# 0x69-2.net
KiCad netlist of a schematic drawn in EAGLE
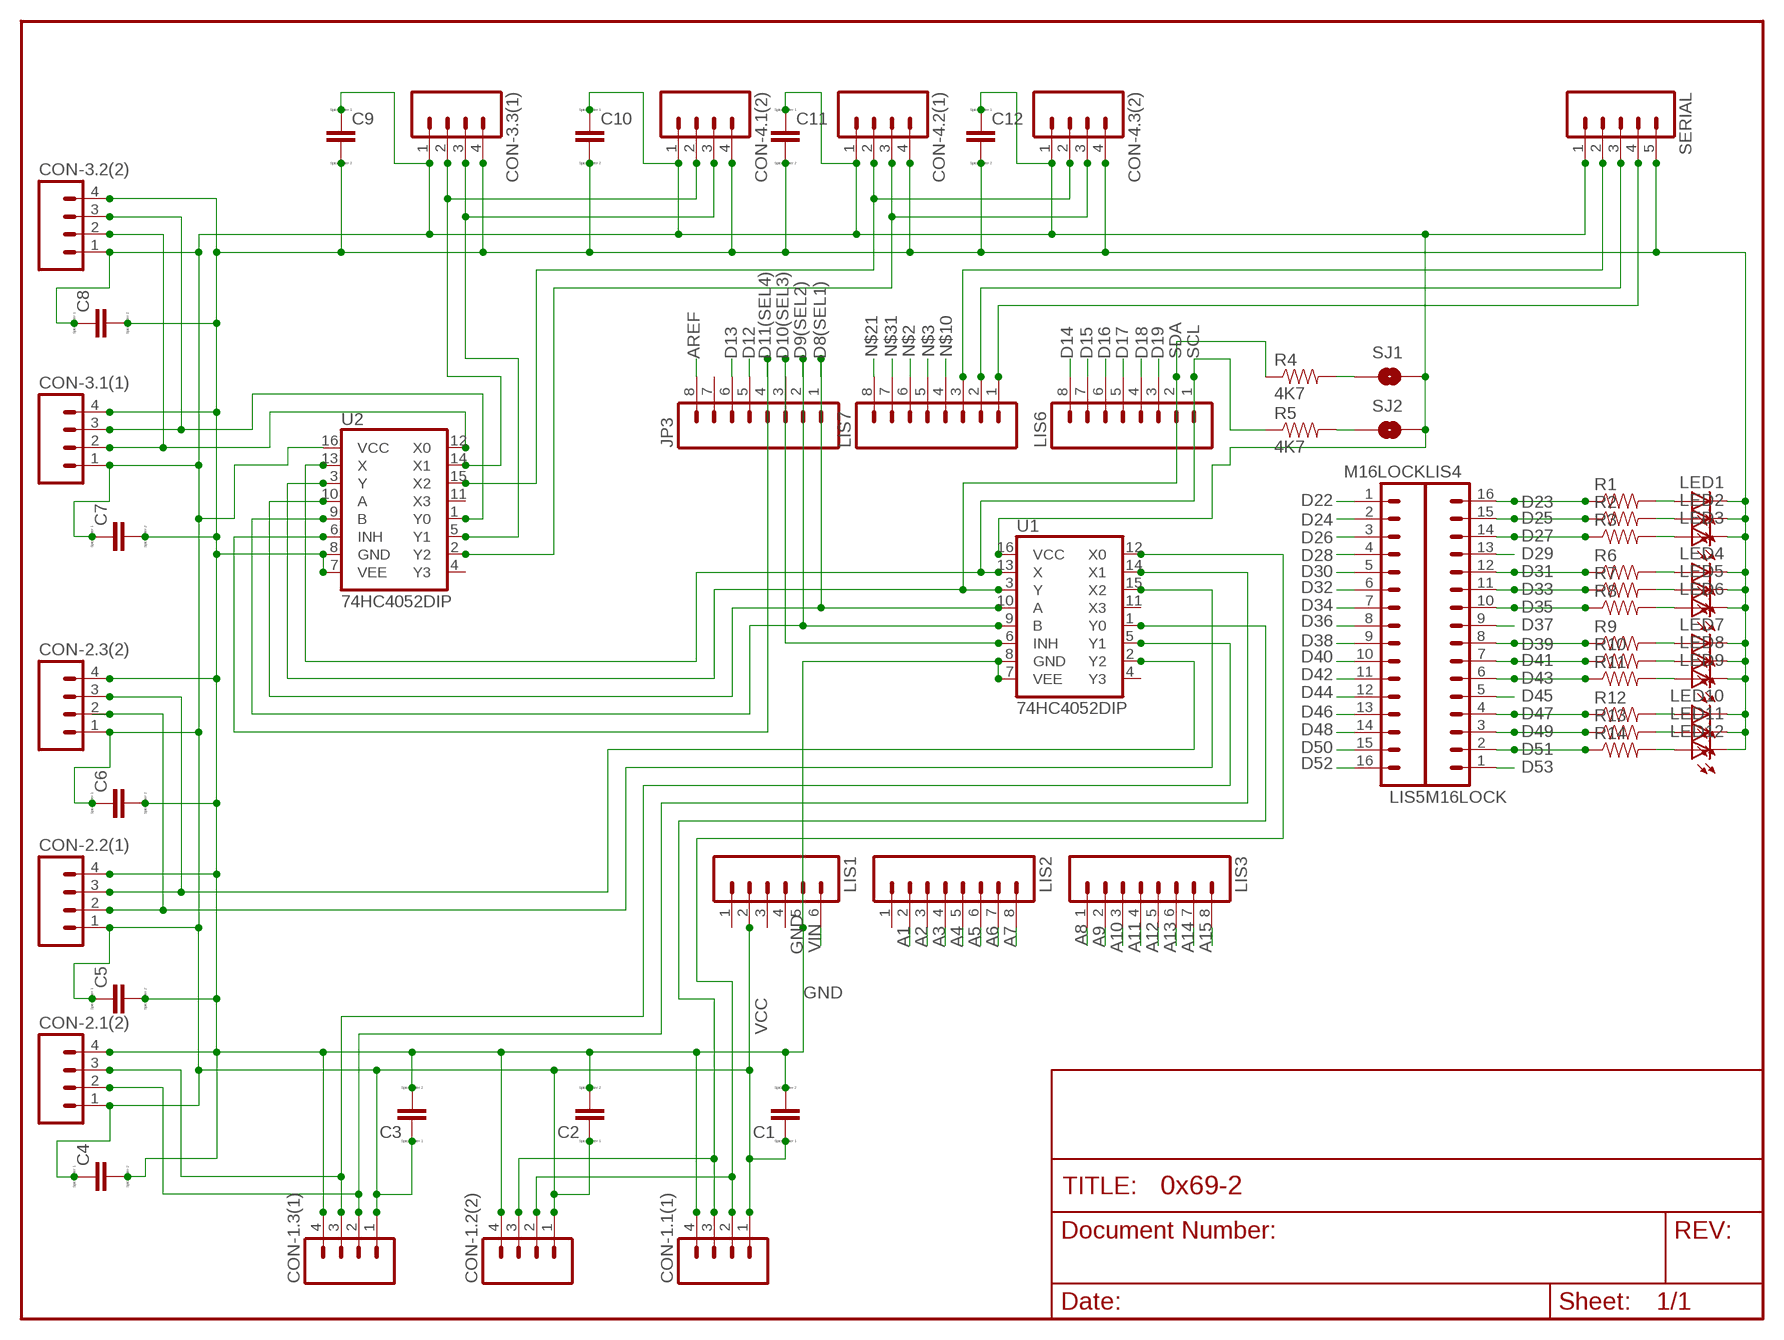
[diagram p0: schematic, sheet 1]

(export (version "E")
  (design (tool "Eeschema 10.0.6"))
  (components
    (comp (ref "C1") (value "C") (footprint "eagle-import:C0805") (libsource (lib "eagle-import") (part "C")))
    (comp (ref "C2") (value "C") (footprint "eagle-import:C0805") (libsource (lib "eagle-import") (part "C")))
    (comp (ref "C3") (value "C") (footprint "eagle-import:C0805") (libsource (lib "eagle-import") (part "C")))
    (comp (ref "C4") (value "C") (footprint "eagle-import:C0805") (libsource (lib "eagle-import") (part "C")))
    (comp (ref "C5") (value "C") (footprint "eagle-import:C0805") (libsource (lib "eagle-import") (part "C")))
    (comp (ref "C6") (value "C") (footprint "eagle-import:C0805") (libsource (lib "eagle-import") (part "C")))
    (comp (ref "C7") (value "C") (footprint "eagle-import:C0805") (libsource (lib "eagle-import") (part "C")))
    (comp (ref "C8") (value "C") (footprint "eagle-import:C0805") (libsource (lib "eagle-import") (part "C")))
    (comp (ref "C9") (value "C") (footprint "eagle-import:C0805") (libsource (lib "eagle-import") (part "C")))
    (comp (ref "C10")
      (value "C")
      (footprint "eagle-import:C0805")
      (libsource (lib "eagle-import") (part "C"))
    )
    (comp (ref "C11")
      (value "C")
      (footprint "eagle-import:C0805")
      (libsource (lib "eagle-import") (part "C"))
    )
    (comp (ref "C12")
      (value "C")
      (footprint "eagle-import:C0805")
      (libsource (lib "eagle-import") (part "C"))
    )
    (comp (ref "CON-1.1(1)")
      (value "M04LONGPADS")
      (footprint "eagle-import:1X04_LONGPADS")
      (libsource (lib "eagle-import") (part "M04LONGPADS"))
    )
    (comp (ref "CON-1.2(2)")
      (value "M04LONGPADS")
      (footprint "eagle-import:1X04_LONGPADS")
      (libsource (lib "eagle-import") (part "M04LONGPADS"))
    )
    (comp (ref "CON-1.3(1)")
      (value "M04LONGPADS")
      (footprint "eagle-import:1X04_LONGPADS")
      (libsource (lib "eagle-import") (part "M04LONGPADS"))
    )
    (comp (ref "CON-2.1(2)")
      (value "M04LONGPADS")
      (footprint "eagle-import:1X04_LONGPADS")
      (libsource (lib "eagle-import") (part "M04LONGPADS"))
    )
    (comp (ref "CON-2.2(1)")
      (value "M04LONGPADS")
      (footprint "eagle-import:1X04_LONGPADS")
      (libsource (lib "eagle-import") (part "M04LONGPADS"))
    )
    (comp (ref "CON-2.3(2)")
      (value "M04LONGPADS")
      (footprint "eagle-import:1X04_LONGPADS")
      (libsource (lib "eagle-import") (part "M04LONGPADS"))
    )
    (comp (ref "CON-3.1(1)")
      (value "M04LONGPADS")
      (footprint "eagle-import:1X04_LONGPADS")
      (libsource (lib "eagle-import") (part "M04LONGPADS"))
    )
    (comp (ref "CON-3.2(2)")
      (value "M04LONGPADS")
      (footprint "eagle-import:1X04_LONGPADS")
      (libsource (lib "eagle-import") (part "M04LONGPADS"))
    )
    (comp (ref "CON-3.3(1)")
      (value "M04LONGPADS")
      (footprint "eagle-import:1X04_LONGPADS")
      (libsource (lib "eagle-import") (part "M04LONGPADS"))
    )
    (comp (ref "CON-4.1(2)")
      (value "M04LONGPADS")
      (footprint "eagle-import:1X04_LONGPADS")
      (libsource (lib "eagle-import") (part "M04LONGPADS"))
    )
    (comp (ref "CON-4.2(1)")
      (value "M04LONGPADS")
      (footprint "eagle-import:1X04_LONGPADS")
      (libsource (lib "eagle-import") (part "M04LONGPADS"))
    )
    (comp (ref "CON-4.3(2)")
      (value "M04LONGPADS")
      (footprint "eagle-import:1X04_LONGPADS")
      (libsource (lib "eagle-import") (part "M04LONGPADS"))
    )
    (comp (ref "JP3")
      (value "M08LOCK")
      (footprint "eagle-import:1X08_LOCK")
      (libsource (lib "eagle-import") (part "M08LOCK"))
    )
    (comp (ref "LED1")
      (value "LED-FKIT-1206")
      (footprint "eagle-import:FKIT-LED-1206")
      (libsource (lib "eagle-import") (part "LED-FKIT-1206"))
    )
    (comp (ref "LED2")
      (value "LED-FKIT-1206")
      (footprint "eagle-import:FKIT-LED-1206")
      (libsource (lib "eagle-import") (part "LED-FKIT-1206"))
    )
    (comp (ref "LED3")
      (value "LED-FKIT-1206")
      (footprint "eagle-import:FKIT-LED-1206")
      (libsource (lib "eagle-import") (part "LED-FKIT-1206"))
    )
    (comp (ref "LED4")
      (value "LED-FKIT-1206")
      (footprint "eagle-import:FKIT-LED-1206")
      (libsource (lib "eagle-import") (part "LED-FKIT-1206"))
    )
    (comp (ref "LED5")
      (value "LED-FKIT-1206")
      (footprint "eagle-import:FKIT-LED-1206")
      (libsource (lib "eagle-import") (part "LED-FKIT-1206"))
    )
    (comp (ref "LED6")
      (value "LED-FKIT-1206")
      (footprint "eagle-import:FKIT-LED-1206")
      (libsource (lib "eagle-import") (part "LED-FKIT-1206"))
    )
    (comp (ref "LED7")
      (value "LED-FKIT-1206")
      (footprint "eagle-import:FKIT-LED-1206")
      (libsource (lib "eagle-import") (part "LED-FKIT-1206"))
    )
    (comp (ref "LED8")
      (value "LED-FKIT-1206")
      (footprint "eagle-import:FKIT-LED-1206")
      (libsource (lib "eagle-import") (part "LED-FKIT-1206"))
    )
    (comp (ref "LED9")
      (value "LED-FKIT-1206")
      (footprint "eagle-import:FKIT-LED-1206")
      (libsource (lib "eagle-import") (part "LED-FKIT-1206"))
    )
    (comp (ref "LED10")
      (value "LED-FKIT-1206")
      (footprint "eagle-import:FKIT-LED-1206")
      (libsource (lib "eagle-import") (part "LED-FKIT-1206"))
    )
    (comp (ref "LED11")
      (value "LED-FKIT-1206")
      (footprint "eagle-import:FKIT-LED-1206")
      (libsource (lib "eagle-import") (part "LED-FKIT-1206"))
    )
    (comp (ref "LED12")
      (value "LED-FKIT-1206")
      (footprint "eagle-import:FKIT-LED-1206")
      (libsource (lib "eagle-import") (part "LED-FKIT-1206"))
    )
    (comp (ref "LIS1")
      (value "M06LOCK")
      (footprint "eagle-import:1X06_LOCK")
      (libsource (lib "eagle-import") (part "M06LOCK"))
    )
    (comp (ref "LIS2")
      (value "M08LOCK")
      (footprint "eagle-import:1X08_LOCK")
      (libsource (lib "eagle-import") (part "M08LOCK"))
    )
    (comp (ref "LIS3")
      (value "M08LOCK")
      (footprint "eagle-import:1X08_LOCK")
      (libsource (lib "eagle-import") (part "M08LOCK"))
    )
    (comp (ref "LIS4")
      (value "M16LOCK")
      (footprint "eagle-import:1X16_LOCK")
      (libsource (lib "eagle-import") (part "M16LOCK"))
    )
    (comp (ref "LIS5")
      (value "M16LOCK")
      (footprint "eagle-import:1X16_LOCK")
      (libsource (lib "eagle-import") (part "M16LOCK"))
    )
    (comp (ref "LIS6")
      (value "M08LOCK")
      (footprint "eagle-import:1X08_LOCK")
      (libsource (lib "eagle-import") (part "M08LOCK"))
    )
    (comp (ref "LIS7")
      (value "M08LOCK")
      (footprint "eagle-import:1X08_LOCK")
      (libsource (lib "eagle-import") (part "M08LOCK"))
    )
    (comp (ref "R1")
      (value "0.22OHM1/4W1%(0805)")
      (footprint "eagle-import:0805")
      (libsource (lib "eagle-import") (part "0.22OHM1/4W1%(0805)"))
    )
    (comp (ref "R2")
      (value "0.22OHM1/4W1%(0805)")
      (footprint "eagle-import:0805")
      (libsource (lib "eagle-import") (part "0.22OHM1/4W1%(0805)"))
    )
    (comp (ref "R3")
      (value "0.22OHM1/4W1%(0805)")
      (footprint "eagle-import:0805")
      (libsource (lib "eagle-import") (part "0.22OHM1/4W1%(0805)"))
    )
    (comp (ref "R4")
      (value "4K7")
      (footprint "eagle-import:0603-RES")
      (libsource (lib "eagle-import") (part "47KOHM1/10W1%(0603)"))
    )
    (comp (ref "R5")
      (value "4K7")
      (footprint "eagle-import:0603-RES")
      (libsource (lib "eagle-import") (part "47KOHM1/10W1%(0603)"))
    )
    (comp (ref "R6")
      (value "0.22OHM1/4W1%(0805)")
      (footprint "eagle-import:0805")
      (libsource (lib "eagle-import") (part "0.22OHM1/4W1%(0805)"))
    )
    (comp (ref "R7")
      (value "0.22OHM1/4W1%(0805)")
      (footprint "eagle-import:0805")
      (libsource (lib "eagle-import") (part "0.22OHM1/4W1%(0805)"))
    )
    (comp (ref "R8")
      (value "0.22OHM1/4W1%(0805)")
      (footprint "eagle-import:0805")
      (libsource (lib "eagle-import") (part "0.22OHM1/4W1%(0805)"))
    )
    (comp (ref "R9")
      (value "0.22OHM1/4W1%(0805)")
      (footprint "eagle-import:0805")
      (libsource (lib "eagle-import") (part "0.22OHM1/4W1%(0805)"))
    )
    (comp (ref "R10")
      (value "0.22OHM1/4W1%(0805)")
      (footprint "eagle-import:0805")
      (libsource (lib "eagle-import") (part "0.22OHM1/4W1%(0805)"))
    )
    (comp (ref "R11")
      (value "0.22OHM1/4W1%(0805)")
      (footprint "eagle-import:0805")
      (libsource (lib "eagle-import") (part "0.22OHM1/4W1%(0805)"))
    )
    (comp (ref "R12")
      (value "0.22OHM1/4W1%(0805)")
      (footprint "eagle-import:0805")
      (libsource (lib "eagle-import") (part "0.22OHM1/4W1%(0805)"))
    )
    (comp (ref "R13")
      (value "0.22OHM1/4W1%(0805)")
      (footprint "eagle-import:0805")
      (libsource (lib "eagle-import") (part "0.22OHM1/4W1%(0805)"))
    )
    (comp (ref "R14")
      (value "0.22OHM1/4W1%(0805)")
      (footprint "eagle-import:0805")
      (libsource (lib "eagle-import") (part "0.22OHM1/4W1%(0805)"))
    )
    (comp (ref "SERIAL")
      (value "M05PTH_LONGPADS")
      (footprint "eagle-import:1X05_LONGPADS")
      (libsource (lib "eagle-import") (part "M05PTH_LONGPADS"))
    )
    (comp (ref "SJ1")
      (value "SOLDERJUMPERNC")
      (footprint "eagle-import:SJ-NC")
      (libsource (lib "eagle-import") (part "SOLDERJUMPERNC"))
    )
    (comp (ref "SJ2")
      (value "SOLDERJUMPERNC")
      (footprint "eagle-import:SJ-NC")
      (libsource (lib "eagle-import") (part "SOLDERJUMPERNC"))
    )
    (comp (ref "U1")
      (value "74HC4052DIP")
      (footprint "eagle-import:DIL16")
      (libsource (lib "eagle-import") (part "74HC4052DIP"))
    )
    (comp (ref "U2")
      (value "74HC4052DIP")
      (footprint "eagle-import:DIL16")
      (libsource (lib "eagle-import") (part "74HC4052DIP"))
    )
  )
  (nets
    (net (code "1") (name "/A1") (class "Default")
      (node (ref "LIS2") (pin "2") (pinfunction "2_2") (pintype "passive"))
    )
    (net (code "2") (name "/A2") (class "Default")
      (node (ref "LIS2") (pin "3") (pinfunction "3_3") (pintype "passive"))
    )
    (net (code "3") (name "/A3") (class "Default")
      (node (ref "LIS2") (pin "4") (pinfunction "4_4") (pintype "passive"))
    )
    (net (code "4") (name "/A4") (class "Default")
      (node (ref "LIS2") (pin "5") (pinfunction "5_5") (pintype "passive"))
    )
    (net (code "5") (name "/A5") (class "Default")
      (node (ref "LIS2") (pin "6") (pinfunction "6_6") (pintype "passive"))
    )
    (net (code "6") (name "/A6") (class "Default")
      (node (ref "LIS2") (pin "7") (pinfunction "7_7") (pintype "passive"))
    )
    (net (code "7") (name "/A7") (class "Default")
      (node (ref "LIS2") (pin "8") (pinfunction "8_8") (pintype "passive"))
    )
    (net (code "8") (name "/A8") (class "Default")
      (node (ref "LIS3") (pin "1") (pinfunction "1_1") (pintype "passive"))
    )
    (net (code "9") (name "/A9") (class "Default")
      (node (ref "LIS3") (pin "2") (pinfunction "2_2") (pintype "passive"))
    )
    (net (code "10") (name "/A10") (class "Default")
      (node (ref "LIS3") (pin "3") (pinfunction "3_3") (pintype "passive"))
    )
    (net (code "11") (name "/A11") (class "Default")
      (node (ref "LIS3") (pin "4") (pinfunction "4_4") (pintype "passive"))
    )
    (net (code "12") (name "/A12") (class "Default")
      (node (ref "LIS3") (pin "5") (pinfunction "5_5") (pintype "passive"))
    )
    (net (code "13") (name "/A13") (class "Default")
      (node (ref "LIS3") (pin "6") (pinfunction "6_6") (pintype "passive"))
    )
    (net (code "14") (name "/A14") (class "Default")
      (node (ref "LIS3") (pin "7") (pinfunction "7_7") (pintype "passive"))
    )
    (net (code "15") (name "/A15") (class "Default")
      (node (ref "LIS3") (pin "8") (pinfunction "8_8") (pintype "passive"))
    )
    (net (code "16") (name "/AREF") (class "Default")
      (node (ref "JP3") (pin "8") (pinfunction "8_8") (pintype "passive"))
    )
    (net (code "17") (name "/D8(SEL1)") (class "Default")
      (node (ref "JP3") (pin "1") (pinfunction "1_1") (pintype "passive"))
      (node (ref "U1") (pin "10") (pinfunction "A_10") (pintype "input"))
      (node (ref "U2") (pin "10") (pinfunction "A_10") (pintype "input"))
    )
    (net (code "18") (name "/D9(SEL2)") (class "Default")
      (node (ref "JP3") (pin "2") (pinfunction "2_2") (pintype "passive"))
      (node (ref "U1") (pin "9") (pinfunction "B_9") (pintype "input"))
      (node (ref "U2") (pin "9") (pinfunction "B_9") (pintype "input"))
    )
    (net (code "19") (name "/D10(SEL3)") (class "Default")
      (node (ref "JP3") (pin "3") (pinfunction "3_3") (pintype "passive"))
      (node (ref "U1") (pin "6") (pinfunction "INH_6") (pintype "input"))
    )
    (net (code "20") (name "/D11(SEL4)") (class "Default")
      (node (ref "JP3") (pin "4") (pinfunction "4_4") (pintype "passive"))
      (node (ref "U2") (pin "6") (pinfunction "INH_6") (pintype "input"))
    )
    (net (code "21") (name "/D12") (class "Default")
      (node (ref "JP3") (pin "5") (pinfunction "5_5") (pintype "passive"))
    )
    (net (code "22") (name "/D13") (class "Default")
      (node (ref "JP3") (pin "6") (pinfunction "6_6") (pintype "passive"))
    )
    (net (code "23") (name "/D14") (class "Default")
      (node (ref "LIS6") (pin "8") (pinfunction "8_8") (pintype "passive"))
    )
    (net (code "24") (name "/D15") (class "Default")
      (node (ref "LIS6") (pin "7") (pinfunction "7_7") (pintype "passive"))
    )
    (net (code "25") (name "/D16") (class "Default")
      (node (ref "LIS6") (pin "6") (pinfunction "6_6") (pintype "passive"))
    )
    (net (code "26") (name "/D17") (class "Default")
      (node (ref "LIS6") (pin "5") (pinfunction "5_5") (pintype "passive"))
    )
    (net (code "27") (name "/D18") (class "Default")
      (node (ref "LIS6") (pin "4") (pinfunction "4_4") (pintype "passive"))
    )
    (net (code "28") (name "/D19") (class "Default")
      (node (ref "LIS6") (pin "3") (pinfunction "3_3") (pintype "passive"))
    )
    (net (code "29") (name "/D22") (class "Default")
      (node (ref "LIS5") (pin "1") (pinfunction "1_1") (pintype "passive"))
    )
    (net (code "30") (name "/D23") (class "Default")
      (node (ref "LIS4") (pin "16") (pinfunction "16_16") (pintype "passive"))
      (node (ref "R1") (pin "1") (pinfunction "1_1") (pintype "passive"))
    )
    (net (code "31") (name "/D24") (class "Default")
      (node (ref "LIS5") (pin "2") (pinfunction "2_2") (pintype "passive"))
    )
    (net (code "32") (name "/D25") (class "Default")
      (node (ref "LIS4") (pin "15") (pinfunction "15_15") (pintype "passive"))
      (node (ref "R2") (pin "1") (pinfunction "1_1") (pintype "passive"))
    )
    (net (code "33") (name "/D26") (class "Default")
      (node (ref "LIS5") (pin "3") (pinfunction "3_3") (pintype "passive"))
    )
    (net (code "34") (name "/D27") (class "Default")
      (node (ref "LIS4") (pin "14") (pinfunction "14_14") (pintype "passive"))
      (node (ref "R3") (pin "1") (pinfunction "1_1") (pintype "passive"))
    )
    (net (code "35") (name "/D28") (class "Default")
      (node (ref "LIS5") (pin "4") (pinfunction "4_4") (pintype "passive"))
    )
    (net (code "36") (name "/D29") (class "Default")
      (node (ref "LIS4") (pin "13") (pinfunction "13_13") (pintype "passive"))
    )
    (net (code "37") (name "/D30") (class "Default")
      (node (ref "LIS5") (pin "5") (pinfunction "5_5") (pintype "passive"))
    )
    (net (code "38") (name "/D31") (class "Default")
      (node (ref "LIS4") (pin "12") (pinfunction "12_12") (pintype "passive"))
      (node (ref "R6") (pin "1") (pinfunction "1_1") (pintype "passive"))
    )
    (net (code "39") (name "/D32") (class "Default")
      (node (ref "LIS5") (pin "6") (pinfunction "6_6") (pintype "passive"))
    )
    (net (code "40") (name "/D33") (class "Default")
      (node (ref "LIS4") (pin "11") (pinfunction "11_11") (pintype "passive"))
      (node (ref "R7") (pin "1") (pinfunction "1_1") (pintype "passive"))
    )
    (net (code "41") (name "/D34") (class "Default")
      (node (ref "LIS5") (pin "7") (pinfunction "7_7") (pintype "passive"))
    )
    (net (code "42") (name "/D35") (class "Default")
      (node (ref "LIS4") (pin "10") (pinfunction "10_10") (pintype "passive"))
      (node (ref "R8") (pin "1") (pinfunction "1_1") (pintype "passive"))
    )
    (net (code "43") (name "/D36") (class "Default")
      (node (ref "LIS5") (pin "8") (pinfunction "8_8") (pintype "passive"))
    )
    (net (code "44") (name "/D37") (class "Default")
      (node (ref "LIS4") (pin "9") (pinfunction "9_9") (pintype "passive"))
    )
    (net (code "45") (name "/D38") (class "Default")
      (node (ref "LIS5") (pin "9") (pinfunction "9_9") (pintype "passive"))
    )
    (net (code "46") (name "/D39") (class "Default")
      (node (ref "LIS4") (pin "8") (pinfunction "8_8") (pintype "passive"))
      (node (ref "R9") (pin "1") (pinfunction "1_1") (pintype "passive"))
    )
    (net (code "47") (name "/D40") (class "Default")
      (node (ref "LIS5") (pin "10") (pinfunction "10_10") (pintype "passive"))
    )
    (net (code "48") (name "/D41") (class "Default")
      (node (ref "LIS4") (pin "7") (pinfunction "7_7") (pintype "passive"))
      (node (ref "R10") (pin "1") (pinfunction "1_1") (pintype "passive"))
    )
    (net (code "49") (name "/D42") (class "Default")
      (node (ref "LIS5") (pin "11") (pinfunction "11_11") (pintype "passive"))
    )
    (net (code "50") (name "/D43") (class "Default")
      (node (ref "LIS4") (pin "6") (pinfunction "6_6") (pintype "passive"))
      (node (ref "R11") (pin "1") (pinfunction "1_1") (pintype "passive"))
    )
    (net (code "51") (name "/D44") (class "Default")
      (node (ref "LIS5") (pin "12") (pinfunction "12_12") (pintype "passive"))
    )
    (net (code "52") (name "/D45") (class "Default")
      (node (ref "LIS4") (pin "5") (pinfunction "5_5") (pintype "passive"))
    )
    (net (code "53") (name "/D46") (class "Default")
      (node (ref "LIS5") (pin "13") (pinfunction "13_13") (pintype "passive"))
    )
    (net (code "54") (name "/D47") (class "Default")
      (node (ref "LIS4") (pin "4") (pinfunction "4_4") (pintype "passive"))
      (node (ref "R12") (pin "1") (pinfunction "1_1") (pintype "passive"))
    )
    (net (code "55") (name "/D48") (class "Default")
      (node (ref "LIS5") (pin "14") (pinfunction "14_14") (pintype "passive"))
    )
    (net (code "56") (name "/D49") (class "Default")
      (node (ref "LIS4") (pin "3") (pinfunction "3_3") (pintype "passive"))
      (node (ref "R13") (pin "1") (pinfunction "1_1") (pintype "passive"))
    )
    (net (code "57") (name "/D50") (class "Default")
      (node (ref "LIS5") (pin "15") (pinfunction "15_15") (pintype "passive"))
    )
    (net (code "58") (name "/D51") (class "Default")
      (node (ref "LIS4") (pin "2") (pinfunction "2_2") (pintype "passive"))
      (node (ref "R14") (pin "1") (pinfunction "1_1") (pintype "passive"))
    )
    (net (code "59") (name "/D52") (class "Default")
      (node (ref "LIS5") (pin "16") (pinfunction "16_16") (pintype "passive"))
    )
    (net (code "60") (name "/D53") (class "Default")
      (node (ref "LIS4") (pin "1") (pinfunction "1_1") (pintype "passive"))
    )
    (net (code "61") (name "/GND") (class "Default")
      (node (ref "C1") (pin "2") (pinfunction "2_2") (pintype "passive"))
      (node (ref "C10") (pin "2") (pinfunction "2_2") (pintype "passive"))
      (node (ref "C11") (pin "2") (pinfunction "2_2") (pintype "passive"))
      (node (ref "C12") (pin "2") (pinfunction "2_2") (pintype "passive"))
      (node (ref "C2") (pin "2") (pinfunction "2_2") (pintype "passive"))
      (node (ref "C3") (pin "2") (pinfunction "2_2") (pintype "passive"))
      (node (ref "C4") (pin "2") (pinfunction "2_2") (pintype "passive"))
      (node (ref "C5") (pin "2") (pinfunction "2_2") (pintype "passive"))
      (node (ref "C6") (pin "2") (pinfunction "2_2") (pintype "passive"))
      (node (ref "C7") (pin "2") (pinfunction "2_2") (pintype "passive"))
      (node (ref "C8") (pin "2") (pinfunction "2_2") (pintype "passive"))
      (node (ref "C9") (pin "2") (pinfunction "2_2") (pintype "passive"))
      (node (ref "CON-1.1(1)") (pin "4") (pinfunction "4_4") (pintype "passive"))
      (node (ref "CON-1.2(2)") (pin "4") (pinfunction "4_4") (pintype "passive"))
      (node (ref "CON-1.3(1)") (pin "4") (pinfunction "4_4") (pintype "passive"))
      (node (ref "CON-2.1(2)") (pin "4") (pinfunction "4_4") (pintype "passive"))
      (node (ref "CON-2.2(1)") (pin "4") (pinfunction "4_4") (pintype "passive"))
      (node (ref "CON-2.3(2)") (pin "4") (pinfunction "4_4") (pintype "passive"))
      (node (ref "CON-3.1(1)") (pin "4") (pinfunction "4_4") (pintype "passive"))
      (node (ref "CON-3.2(2)") (pin "4") (pinfunction "4_4") (pintype "passive"))
      (node (ref "CON-3.3(1)") (pin "4") (pinfunction "4_4") (pintype "passive"))
      (node (ref "CON-4.1(2)") (pin "4") (pinfunction "4_4") (pintype "passive"))
      (node (ref "CON-4.2(1)") (pin "4") (pinfunction "4_4") (pintype "passive"))
      (node (ref "CON-4.3(2)") (pin "4") (pinfunction "4_4") (pintype "passive"))
      (node (ref "LED1") (pin "C") (pinfunction "C_C") (pintype "passive"))
      (node (ref "LED10") (pin "C") (pinfunction "C_C") (pintype "passive"))
      (node (ref "LED11") (pin "C") (pinfunction "C_C") (pintype "passive"))
      (node (ref "LED12") (pin "C") (pinfunction "C_C") (pintype "passive"))
      (node (ref "LED2") (pin "C") (pinfunction "C_C") (pintype "passive"))
      (node (ref "LED3") (pin "C") (pinfunction "C_C") (pintype "passive"))
      (node (ref "LED4") (pin "C") (pinfunction "C_C") (pintype "passive"))
      (node (ref "LED5") (pin "C") (pinfunction "C_C") (pintype "passive"))
      (node (ref "LED6") (pin "C") (pinfunction "C_C") (pintype "passive"))
      (node (ref "LED7") (pin "C") (pinfunction "C_C") (pintype "passive"))
      (node (ref "LED8") (pin "C") (pinfunction "C_C") (pintype "passive"))
      (node (ref "LED9") (pin "C") (pinfunction "C_C") (pintype "passive"))
      (node (ref "LIS1") (pin "5") (pinfunction "5_5") (pintype "passive"))
      (node (ref "SERIAL") (pin "5") (pinfunction "5_5") (pintype "passive"))
      (node (ref "U1") (pin "7") (pinfunction "VEE_7") (pintype "power_in"))
      (node (ref "U1") (pin "8") (pinfunction "GND_8") (pintype "power_in"))
      (node (ref "U2") (pin "7") (pinfunction "VEE_7") (pintype "power_in"))
      (node (ref "U2") (pin "8") (pinfunction "GND_8") (pintype "power_in"))
    )
    (net (code "62") (name "/N$2") (class "Default")
      (node (ref "LIS7") (pin "6") (pinfunction "6_6") (pintype "passive"))
    )
    (net (code "63") (name "/N$3") (class "Default")
      (node (ref "LIS7") (pin "5") (pinfunction "5_5") (pintype "passive"))
    )
    (net (code "64") (name "/N$10") (class "Default")
      (node (ref "LIS7") (pin "4") (pinfunction "4_4") (pintype "passive"))
    )
    (net (code "65") (name "/N$21") (class "Default")
      (node (ref "LIS7") (pin "8") (pinfunction "8_8") (pintype "passive"))
    )
    (net (code "66") (name "/N$31") (class "Default")
      (node (ref "LIS7") (pin "7") (pinfunction "7_7") (pintype "passive"))
    )
    (net (code "67") (name "/SCL") (class "Default")
      (node (ref "LIS6") (pin "1") (pinfunction "1_1") (pintype "passive"))
      (node (ref "R5") (pin "1") (pinfunction "1_1") (pintype "passive"))
      (node (ref "U1") (pin "13") (pinfunction "X_13") (pintype "bidirectional"))
      (node (ref "U2") (pin "13") (pinfunction "X_13") (pintype "bidirectional"))
    )
    (net (code "68") (name "/SDA") (class "Default")
      (node (ref "LIS6") (pin "2") (pinfunction "2_2") (pintype "passive"))
      (node (ref "R4") (pin "1") (pinfunction "1_1") (pintype "passive"))
      (node (ref "U1") (pin "3") (pinfunction "Y_3") (pintype "bidirectional"))
      (node (ref "U2") (pin "3") (pinfunction "Y_3") (pintype "bidirectional"))
    )
    (net (code "69") (name "/VCC") (class "Default")
      (node (ref "C1") (pin "1") (pinfunction "1_1") (pintype "passive"))
      (node (ref "C10") (pin "1") (pinfunction "1_1") (pintype "passive"))
      (node (ref "C11") (pin "1") (pinfunction "1_1") (pintype "passive"))
      (node (ref "C12") (pin "1") (pinfunction "1_1") (pintype "passive"))
      (node (ref "C2") (pin "1") (pinfunction "1_1") (pintype "passive"))
      (node (ref "C3") (pin "1") (pinfunction "1_1") (pintype "passive"))
      (node (ref "C4") (pin "1") (pinfunction "1_1") (pintype "passive"))
      (node (ref "C5") (pin "1") (pinfunction "1_1") (pintype "passive"))
      (node (ref "C6") (pin "1") (pinfunction "1_1") (pintype "passive"))
      (node (ref "C7") (pin "1") (pinfunction "1_1") (pintype "passive"))
      (node (ref "C8") (pin "1") (pinfunction "1_1") (pintype "passive"))
      (node (ref "C9") (pin "1") (pinfunction "1_1") (pintype "passive"))
      (node (ref "CON-1.1(1)") (pin "1") (pinfunction "1_1") (pintype "passive"))
      (node (ref "CON-1.2(2)") (pin "1") (pinfunction "1_1") (pintype "passive"))
      (node (ref "CON-1.3(1)") (pin "1") (pinfunction "1_1") (pintype "passive"))
      (node (ref "CON-2.1(2)") (pin "1") (pinfunction "1_1") (pintype "passive"))
      (node (ref "CON-2.2(1)") (pin "1") (pinfunction "1_1") (pintype "passive"))
      (node (ref "CON-2.3(2)") (pin "1") (pinfunction "1_1") (pintype "passive"))
      (node (ref "CON-3.1(1)") (pin "1") (pinfunction "1_1") (pintype "passive"))
      (node (ref "CON-3.2(2)") (pin "1") (pinfunction "1_1") (pintype "passive"))
      (node (ref "CON-3.3(1)") (pin "1") (pinfunction "1_1") (pintype "passive"))
      (node (ref "CON-4.1(2)") (pin "1") (pinfunction "1_1") (pintype "passive"))
      (node (ref "CON-4.2(1)") (pin "1") (pinfunction "1_1") (pintype "passive"))
      (node (ref "CON-4.3(2)") (pin "1") (pinfunction "1_1") (pintype "passive"))
      (node (ref "LIS1") (pin "2") (pinfunction "2_2") (pintype "passive"))
      (node (ref "SERIAL") (pin "1") (pinfunction "1_1") (pintype "passive"))
      (node (ref "SJ1") (pin "2") (pinfunction "2_2") (pintype "passive"))
      (node (ref "SJ2") (pin "2") (pinfunction "2_2") (pintype "passive"))
      (node (ref "U1") (pin "16") (pinfunction "VCC_16") (pintype "power_in"))
      (node (ref "U2") (pin "16") (pinfunction "VCC_16") (pintype "power_in"))
    )
    (net (code "70") (name "/VIN") (class "Default")
      (node (ref "LIS1") (pin "6") (pinfunction "6_6") (pintype "passive"))
    )
    (net (code "71") (name "Net-(LED1-PadA)") (class "Default")
      (node (ref "LED1") (pin "A") (pinfunction "A_A") (pintype "passive"))
      (node (ref "R1") (pin "2") (pinfunction "2_2") (pintype "passive"))
    )
    (net (code "72") (name "Net-(LED2-PadA)") (class "Default")
      (node (ref "LED2") (pin "A") (pinfunction "A_A") (pintype "passive"))
      (node (ref "R2") (pin "2") (pinfunction "2_2") (pintype "passive"))
    )
    (net (code "73") (name "Net-(LED3-PadA)") (class "Default")
      (node (ref "LED3") (pin "A") (pinfunction "A_A") (pintype "passive"))
      (node (ref "R3") (pin "2") (pinfunction "2_2") (pintype "passive"))
    )
    (net (code "74") (name "Net-(LED4-PadA)") (class "Default")
      (node (ref "LED4") (pin "A") (pinfunction "A_A") (pintype "passive"))
      (node (ref "R6") (pin "2") (pinfunction "2_2") (pintype "passive"))
    )
    (net (code "75") (name "Net-(LED5-PadA)") (class "Default")
      (node (ref "LED5") (pin "A") (pinfunction "A_A") (pintype "passive"))
      (node (ref "R7") (pin "2") (pinfunction "2_2") (pintype "passive"))
    )
    (net (code "76") (name "Net-(LED6-PadA)") (class "Default")
      (node (ref "LED6") (pin "A") (pinfunction "A_A") (pintype "passive"))
      (node (ref "R8") (pin "2") (pinfunction "2_2") (pintype "passive"))
    )
    (net (code "77") (name "Net-(LED7-PadA)") (class "Default")
      (node (ref "LED7") (pin "A") (pinfunction "A_A") (pintype "passive"))
      (node (ref "R9") (pin "2") (pinfunction "2_2") (pintype "passive"))
    )
    (net (code "78") (name "Net-(LED8-PadA)") (class "Default")
      (node (ref "LED8") (pin "A") (pinfunction "A_A") (pintype "passive"))
      (node (ref "R10") (pin "2") (pinfunction "2_2") (pintype "passive"))
    )
    (net (code "79") (name "Net-(LED9-PadA)") (class "Default")
      (node (ref "LED9") (pin "A") (pinfunction "A_A") (pintype "passive"))
      (node (ref "R11") (pin "2") (pinfunction "2_2") (pintype "passive"))
    )
    (net (code "80") (name "Net-(LED10-PadA)") (class "Default")
      (node (ref "LED10") (pin "A") (pinfunction "A_A") (pintype "passive"))
      (node (ref "R12") (pin "2") (pinfunction "2_2") (pintype "passive"))
    )
    (net (code "81") (name "Net-(LED11-PadA)") (class "Default")
      (node (ref "LED11") (pin "A") (pinfunction "A_A") (pintype "passive"))
      (node (ref "R13") (pin "2") (pinfunction "2_2") (pintype "passive"))
    )
    (net (code "82") (name "Net-(LED12-PadA)") (class "Default")
      (node (ref "LED12") (pin "A") (pinfunction "A_A") (pintype "passive"))
      (node (ref "R14") (pin "2") (pinfunction "2_2") (pintype "passive"))
    )
    (net (code "83") (name "Net-(LIS7-Pad1)") (class "Default")
      (node (ref "LIS7") (pin "1") (pinfunction "1_1") (pintype "passive"))
      (node (ref "SERIAL") (pin "4") (pinfunction "4_4") (pintype "passive"))
    )
    (net (code "84") (name "Net-(LIS7-Pad2)") (class "Default")
      (node (ref "LIS7") (pin "2") (pinfunction "2_2") (pintype "passive"))
      (node (ref "SERIAL") (pin "3") (pinfunction "3_3") (pintype "passive"))
    )
    (net (code "85") (name "Net-(LIS7-Pad3)") (class "Default")
      (node (ref "LIS7") (pin "3") (pinfunction "3_3") (pintype "passive"))
      (node (ref "SERIAL") (pin "2") (pinfunction "2_2") (pintype "passive"))
    )
    (net (code "86") (name "Net-(R4-Pad2)") (class "Default")
      (node (ref "R4") (pin "2") (pinfunction "2_2") (pintype "passive"))
      (node (ref "SJ1") (pin "1") (pinfunction "1_1") (pintype "passive"))
    )
    (net (code "87") (name "Net-(R5-Pad2)") (class "Default")
      (node (ref "R5") (pin "2") (pinfunction "2_2") (pintype "passive"))
      (node (ref "SJ2") (pin "1") (pinfunction "1_1") (pintype "passive"))
    )
    (net (code "88") (name "Net-(U1-X0)") (class "Default")
      (node (ref "CON-1.1(1)") (pin "2") (pinfunction "2_2") (pintype "passive"))
      (node (ref "CON-1.2(2)") (pin "2") (pinfunction "2_2") (pintype "passive"))
      (node (ref "U1") (pin "12") (pinfunction "X0_12") (pintype "bidirectional"))
    )
    (net (code "89") (name "Net-(U1-X1)") (class "Default")
      (node (ref "CON-1.3(1)") (pin "2") (pinfunction "2_2") (pintype "passive"))
      (node (ref "CON-2.1(2)") (pin "2") (pinfunction "2_2") (pintype "passive"))
      (node (ref "U1") (pin "14") (pinfunction "X1_14") (pintype "bidirectional"))
    )
    (net (code "90") (name "Net-(U1-X2)") (class "Default")
      (node (ref "CON-2.2(1)") (pin "2") (pinfunction "2_2") (pintype "passive"))
      (node (ref "CON-2.3(2)") (pin "2") (pinfunction "2_2") (pintype "passive"))
      (node (ref "U1") (pin "15") (pinfunction "X2_15") (pintype "bidirectional"))
    )
    (net (code "91") (name "Net-(U1-Y0)") (class "Default")
      (node (ref "CON-1.1(1)") (pin "3") (pinfunction "3_3") (pintype "passive"))
      (node (ref "CON-1.2(2)") (pin "3") (pinfunction "3_3") (pintype "passive"))
      (node (ref "U1") (pin "1") (pinfunction "Y0_1") (pintype "bidirectional"))
    )
    (net (code "92") (name "Net-(U1-Y1)") (class "Default")
      (node (ref "CON-1.3(1)") (pin "3") (pinfunction "3_3") (pintype "passive"))
      (node (ref "CON-2.1(2)") (pin "3") (pinfunction "3_3") (pintype "passive"))
      (node (ref "U1") (pin "5") (pinfunction "Y1_5") (pintype "bidirectional"))
    )
    (net (code "93") (name "Net-(U1-Y2)") (class "Default")
      (node (ref "CON-2.2(1)") (pin "3") (pinfunction "3_3") (pintype "passive"))
      (node (ref "CON-2.3(2)") (pin "3") (pinfunction "3_3") (pintype "passive"))
      (node (ref "U1") (pin "2") (pinfunction "Y2_2") (pintype "bidirectional"))
    )
    (net (code "94") (name "Net-(U2-X0)") (class "Default")
      (node (ref "CON-3.1(1)") (pin "2") (pinfunction "2_2") (pintype "passive"))
      (node (ref "CON-3.2(2)") (pin "2") (pinfunction "2_2") (pintype "passive"))
      (node (ref "U2") (pin "12") (pinfunction "X0_12") (pintype "bidirectional"))
    )
    (net (code "95") (name "Net-(U2-X1)") (class "Default")
      (node (ref "CON-3.3(1)") (pin "2") (pinfunction "2_2") (pintype "passive"))
      (node (ref "CON-4.1(2)") (pin "2") (pinfunction "2_2") (pintype "passive"))
      (node (ref "U2") (pin "14") (pinfunction "X1_14") (pintype "bidirectional"))
    )
    (net (code "96") (name "Net-(U2-X2)") (class "Default")
      (node (ref "CON-4.2(1)") (pin "2") (pinfunction "2_2") (pintype "passive"))
      (node (ref "CON-4.3(2)") (pin "2") (pinfunction "2_2") (pintype "passive"))
      (node (ref "U2") (pin "15") (pinfunction "X2_15") (pintype "bidirectional"))
    )
    (net (code "97") (name "Net-(U2-Y0)") (class "Default")
      (node (ref "CON-3.1(1)") (pin "3") (pinfunction "3_3") (pintype "passive"))
      (node (ref "CON-3.2(2)") (pin "3") (pinfunction "3_3") (pintype "passive"))
      (node (ref "U2") (pin "1") (pinfunction "Y0_1") (pintype "bidirectional"))
    )
    (net (code "98") (name "Net-(U2-Y1)") (class "Default")
      (node (ref "CON-3.3(1)") (pin "3") (pinfunction "3_3") (pintype "passive"))
      (node (ref "CON-4.1(2)") (pin "3") (pinfunction "3_3") (pintype "passive"))
      (node (ref "U2") (pin "5") (pinfunction "Y1_5") (pintype "bidirectional"))
    )
    (net (code "99") (name "Net-(U2-Y2)") (class "Default")
      (node (ref "CON-4.2(1)") (pin "3") (pinfunction "3_3") (pintype "passive"))
      (node (ref "CON-4.3(2)") (pin "3") (pinfunction "3_3") (pintype "passive"))
      (node (ref "U2") (pin "2") (pinfunction "Y2_2") (pintype "bidirectional"))
    )
    (net (code "100") (name "unconnected-(JP3-Pad7)") (class "Default")
      (node (ref "JP3") (pin "7") (pinfunction "7_7") (pintype "passive"))
    )
    (net (code "101") (name "unconnected-(LIS1-Pad1)") (class "Default")
      (node (ref "LIS1") (pin "1") (pinfunction "1_1") (pintype "passive"))
    )
    (net (code "102") (name "unconnected-(LIS1-Pad3)") (class "Default")
      (node (ref "LIS1") (pin "3") (pinfunction "3_3") (pintype "passive"))
    )
    (net (code "103") (name "unconnected-(LIS1-Pad4)") (class "Default")
      (node (ref "LIS1") (pin "4") (pinfunction "4_4") (pintype "passive"))
    )
    (net (code "104") (name "unconnected-(LIS2-Pad1)") (class "Default")
      (node (ref "LIS2") (pin "1") (pinfunction "1_1") (pintype "passive"))
    )
    (net (code "105") (name "unconnected-(U1-X3-Pad11)") (class "Default")
      (node (ref "U1") (pin "11") (pinfunction "X3_11") (pintype "bidirectional"))
    )
    (net (code "106") (name "unconnected-(U1-Y3-Pad4)") (class "Default")
      (node (ref "U1") (pin "4") (pinfunction "Y3_4") (pintype "bidirectional"))
    )
    (net (code "107") (name "unconnected-(U2-X3-Pad11)") (class "Default")
      (node (ref "U2") (pin "11") (pinfunction "X3_11") (pintype "bidirectional"))
    )
    (net (code "108") (name "unconnected-(U2-Y3-Pad4)") (class "Default")
      (node (ref "U2") (pin "4") (pinfunction "Y3_4") (pintype "bidirectional"))
    )
  )
)
